# v1_full_project.net
KiCad netlist of a schematic drawn in EasyEDA Pro
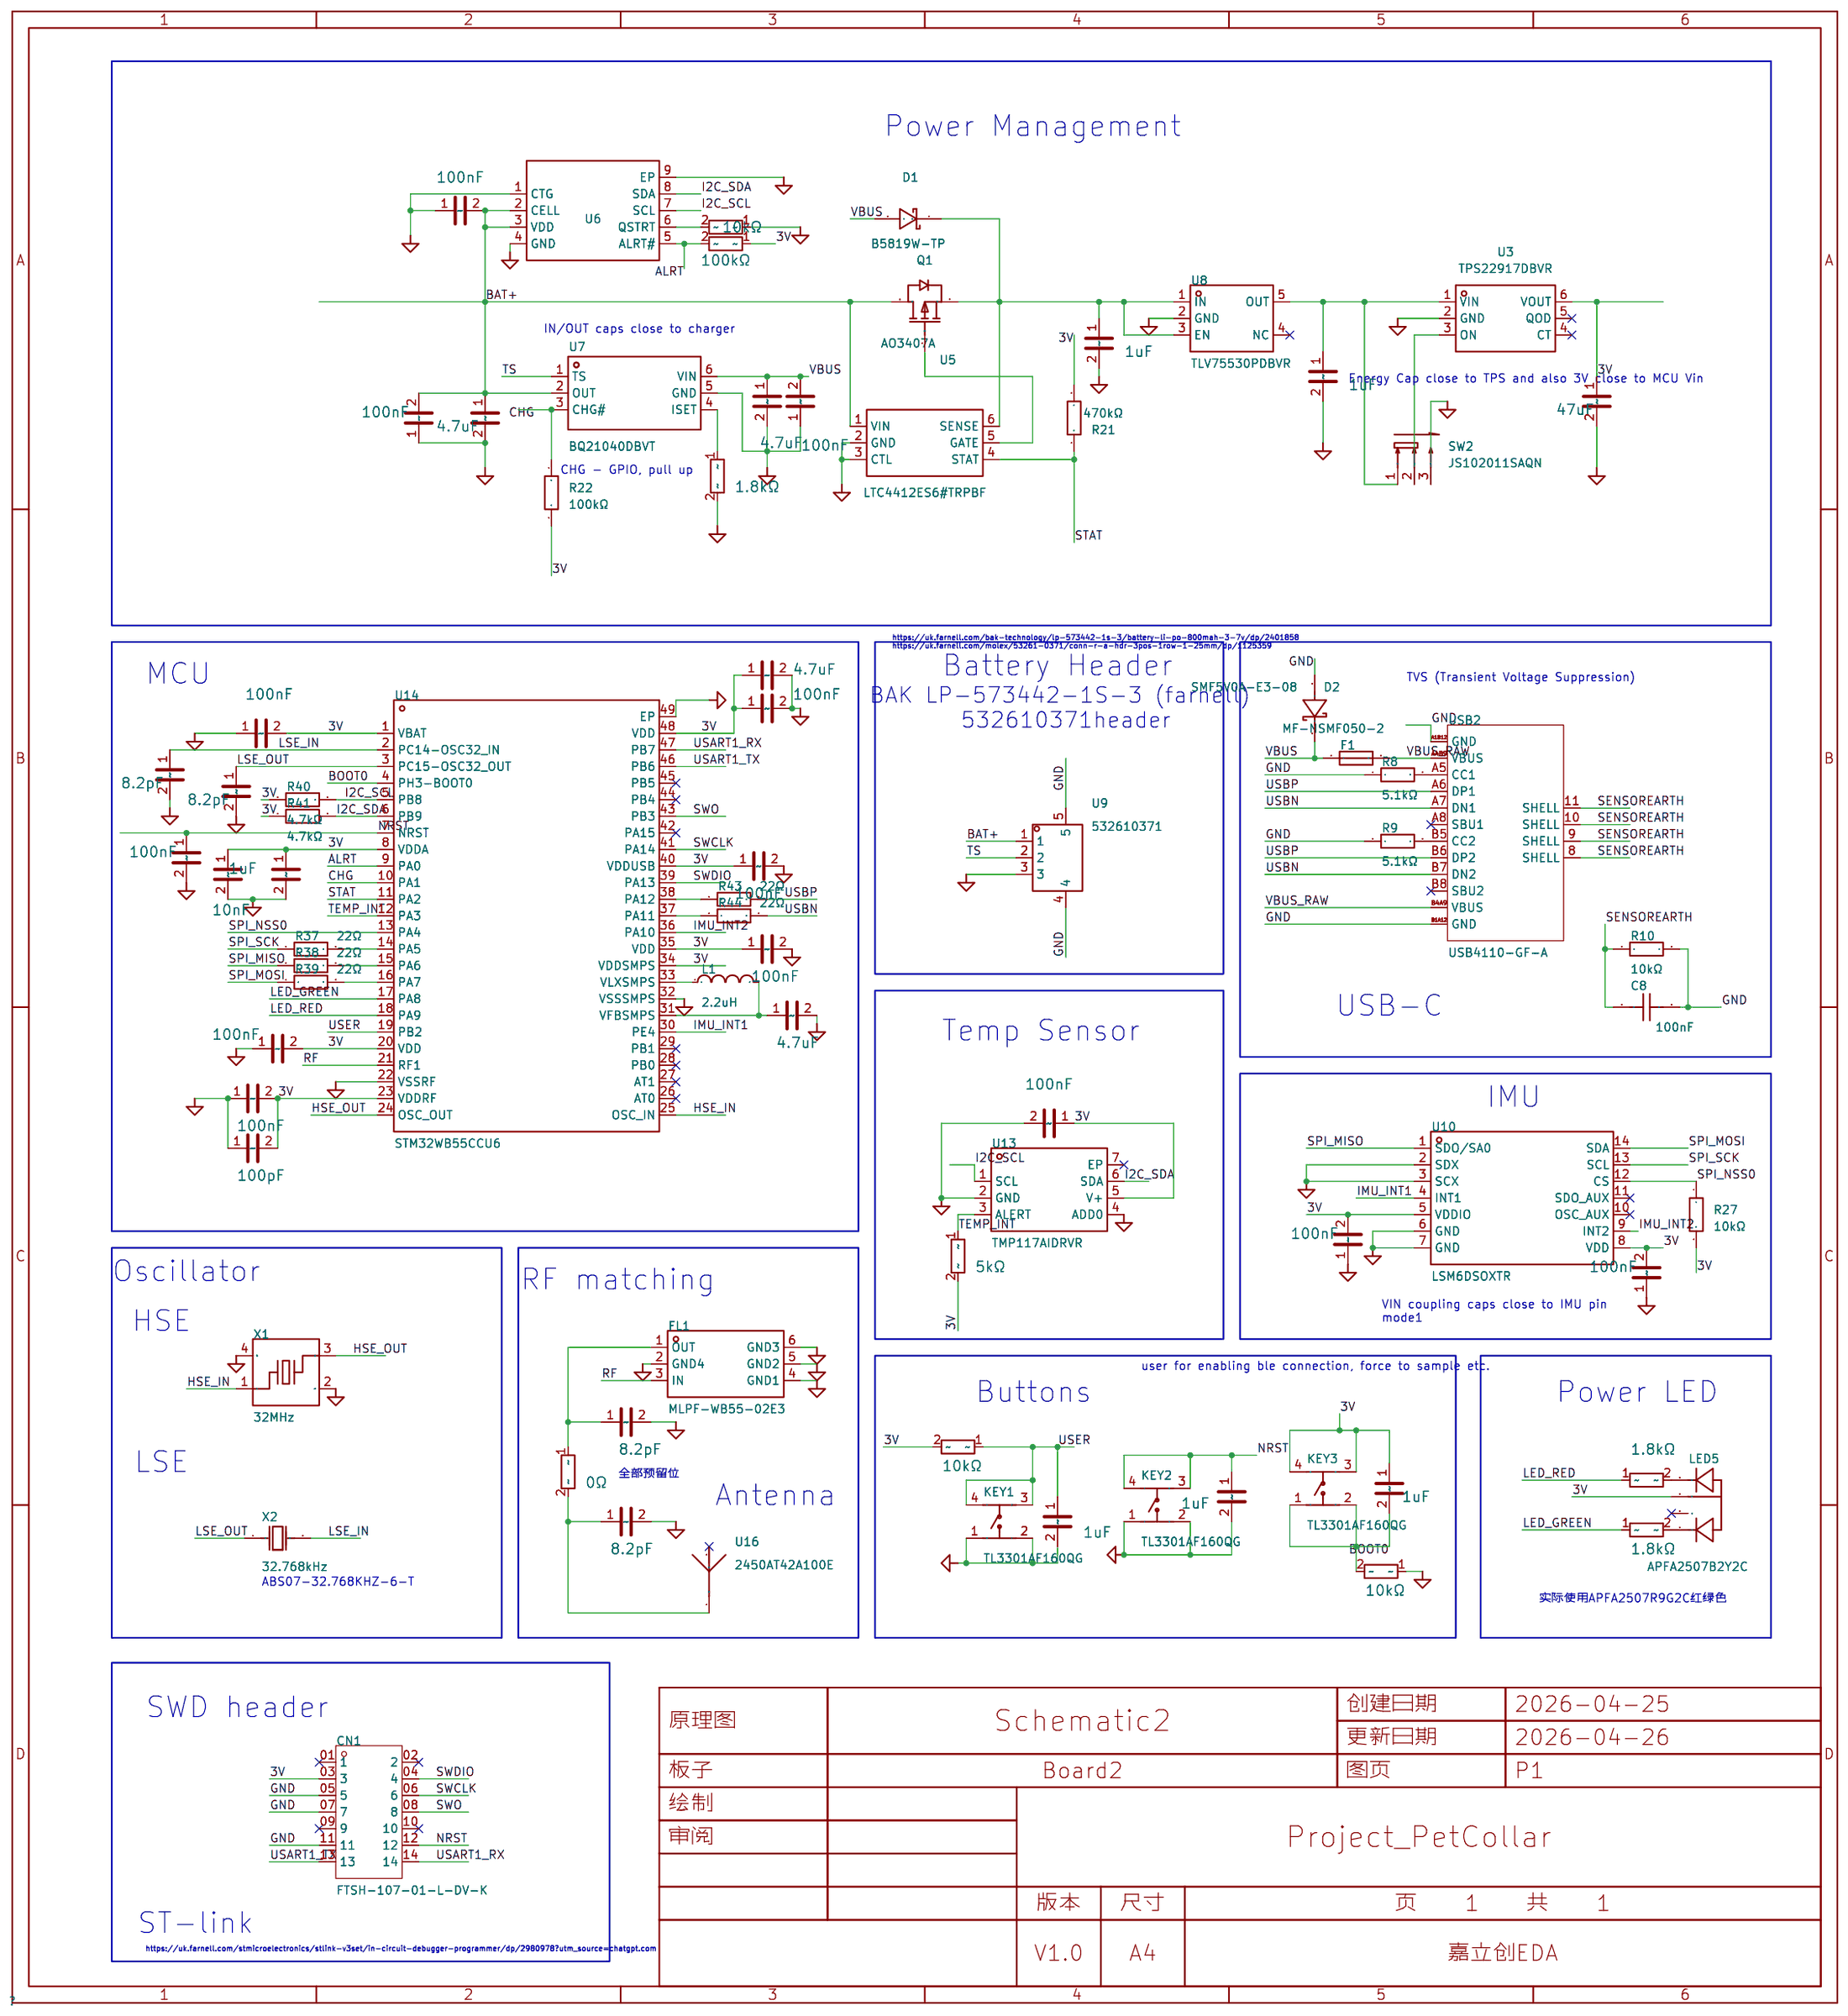
[diagram p0: schematic sheet]

(export (version "E")
  (design (tool "Eeschema 10.0.6"))
  (components
    (comp (ref "C1")
      (value "100nF")
      (description "容值:100nF;精度:±10%;额定电压:50V;温度系数:X7R;")
      (fields
        (field (name "Manufacturer Part") "CL10B104KB8NNNC")
        (field (name "Manufacturer") "SAMSUNG(三星)")
      )
      (libsource (lib "easyedapro") (part "Device_C"))
    )
    (comp (ref "C2")
      (value "1uF")
      (description "容值:1uF;精度:±10%;额定电压:25V;温度系数:X7R;")
      (fields
        (field (name "Manufacturer Part") "CL10B105KA8NNNC")
        (field (name "Manufacturer") "SAMSUNG(三星)")
      )
      (libsource (lib "easyedapro") (part "Device_C"))
    )
    (comp (ref "C3")
      (value "1uF")
      (description "容值:1uF;精度:±10%;额定电压:25V;温度系数:X7R;")
      (fields
        (field (name "Manufacturer Part") "CL10B105KA8NNNC")
        (field (name "Manufacturer") "SAMSUNG(三星)")
      )
      (libsource (lib "easyedapro") (part "Device_C"))
    )
    (comp (ref "C5")
      (value "47uF")
      (description "容值:47uF;精度:±20%;额定电压:6.3V;温度系数:X5R;")
      (fields
        (field (name "Manufacturer Part") "CL21A476MQYNNNE")
        (field (name "Manufacturer") "SAMSUNG(三星)")
      )
      (libsource (lib "easyedapro") (part "Device_C"))
    )
    (comp (ref "C8")
      (value "100nF")
      (fields
        (field (name "Manufacturer Part") "CL10B104KB8NNNC")
        (field (name "Manufacturer") "SAMSUNG(三星)")
      )
      (libsource (lib "easyedapro") (part "Capacitance"))
    )
    (comp (ref "C19")
      (value "1uF")
      (description "容值:1uF;精度:±10%;额定电压:25V;温度系数:X7R;")
      (fields
        (field (name "Manufacturer Part") "CL10B105KA8NNNC")
        (field (name "Manufacturer") "SAMSUNG(三星)")
      )
      (libsource (lib "easyedapro") (part "Device_C"))
    )
    (comp (ref "C23")
      (value "4.7uF")
      (description "容值:4.7uF;精度:±10%;额定电压:16V;温度系数:X5R;")
      (fields
        (field (name "Manufacturer Part") "CL10A475KO8NNNC")
        (field (name "Manufacturer") "SAMSUNG(三星)")
      )
      (libsource (lib "easyedapro") (part "Device_C"))
    )
    (comp (ref "C24")
      (value "4.7uF")
      (description "容值:4.7uF;精度:±10%;额定电压:16V;温度系数:X5R;")
      (fields
        (field (name "Manufacturer Part") "CL10A475KO8NNNC")
        (field (name "Manufacturer") "SAMSUNG(三星)")
      )
      (libsource (lib "easyedapro") (part "Device_C"))
    )
    (comp (ref "C25")
      (value "100nF")
      (description "容值:100nF;精度:±10%;额定电压:50V;温度系数:X7R;")
      (fields
        (field (name "Manufacturer Part") "CL10B104KB8NNNC")
        (field (name "Manufacturer") "SAMSUNG(三星)")
      )
      (libsource (lib "easyedapro") (part "Device_C"))
    )
    (comp (ref "C26")
      (value "100nF")
      (description "容值:100nF;精度:±10%;额定电压:50V;温度系数:X7R;")
      (fields
        (field (name "Manufacturer Part") "CL10B104KB8NNNC")
        (field (name "Manufacturer") "SAMSUNG(三星)")
      )
      (libsource (lib "easyedapro") (part "Device_C"))
    )
    (comp (ref "C27")
      (value "100nF")
      (description "容值:100nF;精度:±10%;额定电压:50V;温度系数:X7R;")
      (fields
        (field (name "Manufacturer Part") "CL10B104KB8NNNC")
        (field (name "Manufacturer") "SAMSUNG(三星)")
      )
      (libsource (lib "easyedapro") (part "Device_C"))
    )
    (comp (ref "C28")
      (value "100nF")
      (description "容值:100nF;精度:±10%;额定电压:50V;温度系数:X7R;")
      (fields
        (field (name "Manufacturer Part") "CL10B104KB8NNNC")
        (field (name "Manufacturer") "SAMSUNG(三星)")
      )
      (libsource (lib "easyedapro") (part "Device_C"))
    )
    (comp (ref "C40")
      (value "1uF")
      (description "容值:1uF;精度:±10%;额定电压:25V;温度系数:X7R;")
      (fields
        (field (name "Manufacturer Part") "CL10B105KA8NNNC")
        (field (name "Manufacturer") "SAMSUNG(三星)")
      )
      (libsource (lib "easyedapro") (part "Device_C"))
    )
    (comp (ref "C41")
      (value "100nF")
      (description "容值:100nF;精度:±10%;额定电压:50V;温度系数:X7R;")
      (fields
        (field (name "Manufacturer Part") "CL10B104KB8NNNC")
        (field (name "Manufacturer") "SAMSUNG(三星)")
      )
      (libsource (lib "easyedapro") (part "Device_C"))
    )
    (comp (ref "C42")
      (value "8.2pF")
      (description "容值:8.2pF;额定电压:50V;材质(温度系数):C0G;")
      (fields
        (field (name "Manufacturer Part") "GJM1555C1H8R2BB01D")
        (field (name "Manufacturer") "muRata(村田)")
      )
      (libsource (lib "easyedapro") (part "Device_C"))
    )
    (comp (ref "C43")
      (value "8.2pF")
      (description "容值:8.2pF;额定电压:50V;材质(温度系数):C0G;")
      (fields
        (field (name "Manufacturer Part") "GJM1555C1H8R2BB01D")
        (field (name "Manufacturer") "muRata(村田)")
      )
      (libsource (lib "easyedapro") (part "Device_C"))
    )
    (comp (ref "C46")
      (value "4.7uF")
      (description "容值:4.7uF;精度:±10%;额定电压:16V;温度系数:X5R;")
      (fields
        (field (name "Manufacturer Part") "CL10A475KO8NNNC")
        (field (name "Manufacturer") "SAMSUNG(三星)")
      )
      (libsource (lib "easyedapro") (part "Device_C"))
    )
    (comp (ref "C49")
      (value "100nF")
      (description "容值:100nF;精度:±10%;额定电压:50V;温度系数:X7R;")
      (fields
        (field (name "Manufacturer Part") "CL10B104KB8NNNC")
        (field (name "Manufacturer") "SAMSUNG(三星)")
      )
      (libsource (lib "easyedapro") (part "Device_C"))
    )
    (comp (ref "C50")
      (value "100nF")
      (description "容值:100nF;精度:±10%;额定电压:50V;温度系数:X7R;")
      (fields
        (field (name "Manufacturer Part") "CL10B104KB8NNNC")
        (field (name "Manufacturer") "SAMSUNG(三星)")
      )
      (libsource (lib "easyedapro") (part "Device_C"))
    )
    (comp (ref "C51")
      (value "100nF")
      (description "容值:100nF;精度:±10%;额定电压:50V;温度系数:X7R;")
      (fields
        (field (name "Manufacturer Part") "CL10B104KB8NNNC")
        (field (name "Manufacturer") "SAMSUNG(三星)")
      )
      (libsource (lib "easyedapro") (part "Device_C"))
    )
    (comp (ref "C52")
      (value "4.7uF")
      (description "容值:4.7uF;精度:±10%;额定电压:16V;温度系数:X5R;")
      (fields
        (field (name "Manufacturer Part") "CL10A475KO8NNNC")
        (field (name "Manufacturer") "SAMSUNG(三星)")
      )
      (libsource (lib "easyedapro") (part "Device_C"))
    )
    (comp (ref "C53")
      (value "10nF")
      (description "容值:10nF;精度:±5%;额定电压:50V;材质(温度系数):C0G;")
      (fields
        (field (name "Manufacturer Part") "GRM1885C1H103JA01D")
        (field (name "Manufacturer") "muRata(村田)")
      )
      (libsource (lib "easyedapro") (part "Device_C"))
    )
    (comp (ref "C54")
      (value "1uF")
      (description "容值:1uF;精度:±10%;额定电压:25V;温度系数:X7R;")
      (fields
        (field (name "Manufacturer Part") "CL10B105KA8NNNC")
        (field (name "Manufacturer") "SAMSUNG(三星)")
      )
      (libsource (lib "easyedapro") (part "Device_C"))
    )
    (comp (ref "C55")
      (value "100nF")
      (description "容值:100nF;精度:±10%;额定电压:50V;温度系数:X7R;")
      (fields
        (field (name "Manufacturer Part") "CL10B104KB8NNNC")
        (field (name "Manufacturer") "SAMSUNG(三星)")
      )
      (libsource (lib "easyedapro") (part "Device_C"))
    )
    (comp (ref "C56")
      (value "100nF")
      (description "容值:100nF;精度:±10%;额定电压:50V;温度系数:X7R;")
      (fields
        (field (name "Manufacturer Part") "CL10B104KB8NNNC")
        (field (name "Manufacturer") "SAMSUNG(三星)")
      )
      (libsource (lib "easyedapro") (part "Device_C"))
    )
    (comp (ref "C57")
      (value "100pF")
      (description "容值:100pF;精度:±5%;额定电压:50V;温度系数:C0G;")
      (fields
        (field (name "Manufacturer Part") "CL10C101JB8NNNC")
        (field (name "Manufacturer") "SAMSUNG(三星)")
      )
      (libsource (lib "easyedapro") (part "Device_C"))
    )
    (comp (ref "C58")
      (value "100nF")
      (description "容值:100nF;精度:±10%;额定电压:50V;温度系数:X7R;")
      (fields
        (field (name "Manufacturer Part") "CL10B104KB8NNNC")
        (field (name "Manufacturer") "SAMSUNG(三星)")
      )
      (libsource (lib "easyedapro") (part "Device_C"))
    )
    (comp (ref "C59")
      (value "100nF")
      (description "容值:100nF;精度:±10%;额定电压:50V;温度系数:X7R;")
      (fields
        (field (name "Manufacturer Part") "CL10B104KB8NNNC")
        (field (name "Manufacturer") "SAMSUNG(三星)")
      )
      (libsource (lib "easyedapro") (part "Device_C"))
    )
    (comp (ref "C60")
      (value "1uF")
      (description "容值:1uF;精度:±10%;额定电压:25V;温度系数:X7R;")
      (fields
        (field (name "Manufacturer Part") "CL10B105KA8NNNC")
        (field (name "Manufacturer") "SAMSUNG(三星)")
      )
      (libsource (lib "easyedapro") (part "Device_C"))
    )
    (comp (ref "C61")
      (value "8.2pF")
      (description "容值:8.2pF;额定电压:50V;材质(温度系数):C0G;")
      (fields
        (field (name "Manufacturer Part") "GJM1555C1H8R2BB01D")
        (field (name "Manufacturer") "muRata(村田)")
      )
      (libsource (lib "easyedapro") (part "Device_C"))
    )
    (comp (ref "C62")
      (value "8.2pF")
      (description "容值:8.2pF;额定电压:50V;材质(温度系数):C0G;")
      (fields
        (field (name "Manufacturer Part") "GJM1555C1H8R2BB01D")
        (field (name "Manufacturer") "muRata(村田)")
      )
      (libsource (lib "easyedapro") (part "Device_C"))
    )
    (comp (ref "CN1")
      (value "FTSH-107-01-L-DV-K")
      (footprint "easyedapro:HDR-SMD_14P-P1.27_FTSH-107-01-L-DV-K")
      (fields (field (name "Manufacturer") "SAMTEC"))
      (libsource (lib "easyedapro") (part "FTSH-107-01-L-DV-K"))
    )
    (comp (ref "D1")
      (value "B5819W-TP")
      (footprint "easyedapro:SOD-123_L2.8-W1.8-LS3.7-RD")
      (description "二极管配置:-;正向压降(Vf):600mV@1A;直流反向耐压(Vr):40V;整流电流:1A;")
      (fields (field (name "Manufacturer") "MCC(美微科)"))
      (libsource (lib "easyedapro") (part "B5819W-TP"))
    )
    (comp (ref "D2")
      (value "SMF5V0A-E3-08")
      (footprint "easyedapro:SMF_L2.8-W1.8-LS3.7-RD")
      (fields (field (name "Manufacturer") "VISHAY(威世)"))
      (libsource (lib "easyedapro") (part "SMF5V0A-E3-08"))
    )
    (comp (ref "F1")
      (value "MF-NSMF050-2")
      (footprint "easyedapro:F1206")
      (fields (field (name "Manufacturer") "BOURNS"))
      (libsource (lib "easyedapro") (part "MF-NSMF050-2"))
    )
    (comp (ref "FL1")
      (value "MLPF-WB55-02E3")
      (footprint "easyedapro:FILTER-SMD_6P-L1.6-W1.0-P0.50-BL")
      (fields (field (name "Manufacturer") "ST(意法半导体)"))
      (libsource (lib "easyedapro") (part "MLPF-WB55-02E3"))
    )
    (comp (ref "KEY1")
      (value "TL3301AF160QG")
      (footprint "easyedapro:KEY-SMD_4P-L6.0-W6.0-P4.50-LS10.0")
      (fields (field (name "Manufacturer") "E-Switch"))
      (libsource (lib "easyedapro") (part "TL3301AF160QG"))
    )
    (comp (ref "KEY2")
      (value "TL3301AF160QG")
      (footprint "easyedapro:KEY-SMD_4P-L6.0-W6.0-P4.50-LS10.0")
      (fields (field (name "Manufacturer") "E-Switch"))
      (libsource (lib "easyedapro") (part "TL3301AF160QG"))
    )
    (comp (ref "KEY3")
      (value "TL3301AF160QG")
      (footprint "easyedapro:KEY-SMD_4P-L6.0-W6.0-P4.50-LS10.0")
      (fields (field (name "Manufacturer") "E-Switch"))
      (libsource (lib "easyedapro") (part "TL3301AF160QG"))
    )
    (comp (ref "L1")
      (value "2.2uH")
      (footprint "easyedapro:L1008")
      (fields
        (field (name "Manufacturer Part") "1239AS-H-2R2M=P2")
        (field (name "Manufacturer") "muRata(村田)")
      )
      (libsource (lib "easyedapro") (part "1239AS-H-2R2M=P2"))
    )
    (comp (ref "LED5")
      (value "APFA2507B2Y2C")
      (footprint "easyedapro:LED-SMD_4P-L2.5-W1.0_APFA2507LQBDSEEZGKC")
      (fields (field (name "Manufacturer") "Kingbright"))
      (libsource (lib "easyedapro") (part "APFA2507B2Y2C"))
    )
    (comp (ref "Q1")
      (value "AO3407A")
      (footprint "easyedapro:SOT-23-3_L2.9-W1.6-P1.90-LS2.8-BR")
      (fields (field (name "Manufacturer") "AOS"))
      (libsource (lib "easyedapro") (part "AO3407A"))
    )
    (comp (ref "R1")
      (value "10kΩ")
      (description "电阻类型:厚膜电阻;阻值:10kΩ;精度:±1%;功率:100mW;最大工作电压:75V;温度系数:±100ppm/℃;")
      (fields (field (name "Manufacturer Part") "RC0603FR-0710KL") (field (name "Manufacturer") "YAGEO(国巨)"))
      (libsource (lib "easyedapro") (part "Device_R"))
    )
    (comp (ref "R2")
      (value "100kΩ")
      (description "电阻类型:厚膜电阻;阻值:100kΩ;精度:±1%;功率:100mW;最大工作电压:75V;温度系数:±100ppm/℃;")
      (fields (field (name "Manufacturer Part") "RC0603FR-07100KL") (field (name "Manufacturer") "YAGEO(国巨)"))
      (libsource (lib "easyedapro") (part "Device_R"))
    )
    (comp (ref "R8")
      (value "5.1kΩ")
      (fields (field (name "Manufacturer Part") "FRC0603F5102TS") (field (name "Manufacturer") "FOJAN(富捷)"))
      (libsource (lib "easyedapro") (part "电阻"))
    )
    (comp (ref "R9")
      (value "5.1kΩ")
      (fields (field (name "Manufacturer Part") "FRC0603F5102TS") (field (name "Manufacturer") "FOJAN(富捷)"))
      (libsource (lib "easyedapro") (part "电阻"))
    )
    (comp (ref "R10")
      (value "10kΩ")
      (fields (field (name "Manufacturer Part") "RC0603FR-0710KL") (field (name "Manufacturer") "YAGEO(国巨)"))
      (libsource (lib "easyedapro") (part "电阻"))
    )
    (comp (ref "R20")
      (value "1.8kΩ")
      (description "电阻类型:厚膜电阻;阻值:1.8kΩ;精度:±1%;功率:100mW;工作电压:75V;温度系数:±100ppm/℃;")
      (fields
        (field (name "Manufacturer Part") "0603WAF1801T5E")
        (field (name "Manufacturer") "UNI-ROYAL(厚声)")
      )
      (libsource (lib "easyedapro") (part "Device_R"))
    )
    (comp (ref "R21")
      (value "470kΩ")
      (fields (field (name "Manufacturer Part") "FRC0603F4703TS") (field (name "Manufacturer") "FOJAN(富捷)"))
      (libsource (lib "easyedapro") (part "电阻"))
    )
    (comp (ref "R22")
      (value "100kΩ")
      (fields (field (name "Manufacturer Part") "RC0603FR-07100KL") (field (name "Manufacturer") "YAGEO(国巨)"))
      (libsource (lib "easyedapro") (part "电阻"))
    )
    (comp (ref "R27")
      (value "10kΩ")
      (fields (field (name "Manufacturer Part") "RC0603FR-0710KL") (field (name "Manufacturer") "YAGEO(国巨)"))
      (libsource (lib "easyedapro") (part "电阻"))
    )
    (comp (ref "R33")
      (value "10kΩ")
      (description "电阻类型:厚膜电阻;阻值:10kΩ;精度:±1%;功率:100mW;最大工作电压:75V;温度系数:±100ppm/℃;")
      (fields (field (name "Manufacturer Part") "RC0603FR-0710KL") (field (name "Manufacturer") "YAGEO(国巨)"))
      (libsource (lib "easyedapro") (part "Device_R"))
    )
    (comp (ref "R35")
      (value "5kΩ")
      (description "电阻类型:薄膜电阻;阻值:5kΩ;精度:±0.1%;功率:100mW;温度系数:±50ppm/℃;")
      (fields (field (name "Manufacturer Part") "RT0603BRE075KL") (field (name "Manufacturer") "YAGEO(国巨)"))
      (libsource (lib "easyedapro") (part "Device_R"))
    )
    (comp (ref "R36")
      (value "0Ω")
      (description "电阻类型:厚膜电阻;阻值:0Ω;精度:±1%;功率:62.5mW;工作电压:50V;温度系数:-;")
      (fields (field (name "Manufacturer Part") "RC0402FR-070RL") (field (name "Manufacturer") "YAGEO(国巨)"))
      (libsource (lib "easyedapro") (part "Device_R"))
    )
    (comp (ref "R37")
      (value "22Ω")
      (fields (field (name "Manufacturer Part") "FRC0603J220 TS") (field (name "Manufacturer") "FOJAN(富捷)"))
      (libsource (lib "easyedapro") (part "电阻"))
    )
    (comp (ref "R38")
      (value "22Ω")
      (fields (field (name "Manufacturer Part") "FRC0603J220 TS") (field (name "Manufacturer") "FOJAN(富捷)"))
      (libsource (lib "easyedapro") (part "电阻"))
    )
    (comp (ref "R39")
      (value "22Ω")
      (fields (field (name "Manufacturer Part") "FRC0603J220 TS") (field (name "Manufacturer") "FOJAN(富捷)"))
      (libsource (lib "easyedapro") (part "电阻"))
    )
    (comp (ref "R40")
      (value "4.7kΩ")
      (fields (field (name "Manufacturer Part") "RC0603FR-074K7L") (field (name "Manufacturer") "YAGEO(国巨)"))
      (libsource (lib "easyedapro") (part "电阻"))
    )
    (comp (ref "R41")
      (value "4.7kΩ")
      (fields (field (name "Manufacturer Part") "RC0603FR-074K7L") (field (name "Manufacturer") "YAGEO(国巨)"))
      (libsource (lib "easyedapro") (part "电阻"))
    )
    (comp (ref "R42")
      (value "10kΩ")
      (description "电阻类型:厚膜电阻;阻值:10kΩ;精度:±1%;功率:100mW;最大工作电压:75V;温度系数:±100ppm/℃;")
      (fields (field (name "Manufacturer Part") "RC0603FR-0710KL") (field (name "Manufacturer") "YAGEO(国巨)"))
      (libsource (lib "easyedapro") (part "Device_R"))
    )
    (comp (ref "R43")
      (value "22Ω")
      (fields (field (name "Manufacturer Part") "FRC0603J220 TS") (field (name "Manufacturer") "FOJAN(富捷)"))
      (libsource (lib "easyedapro") (part "电阻"))
    )
    (comp (ref "R44")
      (value "22Ω")
      (fields (field (name "Manufacturer Part") "FRC0603J220 TS") (field (name "Manufacturer") "FOJAN(富捷)"))
      (libsource (lib "easyedapro") (part "电阻"))
    )
    (comp (ref "R45")
      (value "1.8kΩ")
      (description "电阻类型:厚膜电阻;阻值:1.8kΩ;精度:±1%;功率:100mW;工作电压:75V;温度系数:±100ppm/℃;")
      (fields
        (field (name "Manufacturer Part") "0603WAF1801T5E")
        (field (name "Manufacturer") "UNI-ROYAL(厚声)")
      )
      (libsource (lib "easyedapro") (part "Device_R"))
    )
    (comp (ref "R46")
      (value "1.8kΩ")
      (description "电阻类型:厚膜电阻;阻值:1.8kΩ;精度:±1%;功率:100mW;工作电压:75V;温度系数:±100ppm/℃;")
      (fields
        (field (name "Manufacturer Part") "0603WAF1801T5E")
        (field (name "Manufacturer") "UNI-ROYAL(厚声)")
      )
      (libsource (lib "easyedapro") (part "Device_R"))
    )
    (comp (ref "SW2")
      (value "JS102011SAQN")
      (footprint "easyedapro:SW-SMD_JS102011SAQN")
      (fields (field (name "Manufacturer") "C&K"))
      (libsource (lib "easyedapro") (part "JS102011SAQN"))
    )
    (comp (ref "U3")
      (value "TPS22917DBVR")
      (footprint "easyedapro:SOT-23-6_L2.9-W1.6-P0.95-LS2.8-BR")
      (description "类型:负载开关;通道数:1;输入控制逻辑:高电平有效;最大连续电流:2A;工作电压:0V~5.5V;导通电阻:80mΩ;")
      (fields (field (name "Manufacturer") "TI(德州仪器)"))
      (libsource (lib "easyedapro") (part "TPS22917DBVR"))
    )
    (comp (ref "U5")
      (value "LTC4412ES6#TRPBF")
      (footprint "easyedapro:TSOT-23-6_L2.9-W1.6-P0.95-LS2.8-BR")
      (description "负载类型:MOSFET;工作电压:2.5V~28V;")
      (fields (field (name "Manufacturer") "ADI(亚德诺)"))
      (libsource (lib "easyedapro") (part "LTC4412ES6#TRPBF"))
    )
    (comp (ref "U6")
      (value "MAX17048G+T10")
      (footprint "easyedapro:TDFN-8_L2.0-W2.0-P0.50-BL-EP1.2")
      (description "工作电压:2.5V~4.5V;电池类型:锂离子/聚合物;电池节数:1;")
      (fields (field (name "Manufacturer") "ADI(亚德诺)/MAXIM(美信)"))
      (libsource (lib "easyedapro") (part "MAX17048G+T10"))
    )
    (comp (ref "U7")
      (value "BQ21040DBVT")
      (footprint "easyedapro:SOT-23-6_L2.9-W1.6-P0.95-LS2.8-BR")
      (fields (field (name "Manufacturer") "TI(德州仪器)"))
      (libsource (lib "easyedapro") (part "BQ21040DBVT"))
    )
    (comp (ref "U8")
      (value "TLV75530PDBVR")
      (footprint "easyedapro:SOT-23-5_L3.0-W1.7-P0.95-LS2.8-BR")
      (fields (field (name "Manufacturer") "TI(德州仪器)"))
      (libsource (lib "easyedapro") (part "TLV75530PDBVR"))
    )
    (comp (ref "U9")
      (value "532610371")
      (footprint "easyedapro:CONN-TH_532610371")
      (fields (field (name "Manufacturer") "MOLEX"))
      (libsource (lib "easyedapro") (part "532610371"))
    )
    (comp (ref "U10")
      (value "LSM6DSOXTR")
      (footprint "easyedapro:LGA-14L_L3.0-W2.5-P0.50-TL")
      (fields (field (name "Manufacturer") "ST(意法半导体)"))
      (libsource (lib "easyedapro") (part "LSM6DSOXTR"))
    )
    (comp (ref "U13")
      (value "TMP117AIDRVR")
      (footprint "easyedapro:WSON-6_L2.0-W2.0-P0.65-TL-EP")
      (fields (field (name "Manufacturer") "TI(德州仪器)"))
      (libsource (lib "easyedapro") (part "TMP117AIDRVR"))
    )
    (comp (ref "U14")
      (value "STM32WB55CCU6")
      (footprint "easyedapro:VQFN-48_L7.0-W7.0-P0.50-BL-EP5.5")
      (fields (field (name "Manufacturer") "ST(意法半导体)"))
      (libsource (lib "easyedapro") (part "STM32WB55CCU6"))
    )
    (comp (ref "U16")
      (value "2450AT42A100E")
      (footprint "easyedapro:ANT-SMD_L5.0-W2.0")
      (fields (field (name "Manufacturer") "JOHANSON(约翰逊)"))
      (libsource (lib "easyedapro") (part "2450AT42A100E"))
    )
    (comp (ref "USB2")
      (value "USB4110-GF-A")
      (footprint "easyedapro:USB-C-SMD_TYPE-C-16P-USB4110-GF-A")
      (description "连接器类型:Type-C;协议标准:USB 2.0;公母:母;安装方式:卧贴;端口数量:1;额定电流 - 电源:5A;工作温度:-40°C~+85°C;")
      (fields (field (name "Manufacturer") "GCT"))
      (libsource (lib "easyedapro") (part "USB4110-GF-A"))
    )
    (comp (ref "X1")
      (value "32MHz")
      (footprint "easyedapro:CRYSTAL-SMD_4P-L2.0-W1.6-BL")
      (fields
        (field (name "Manufacturer Part") "NX2016SA-32MHZ-EXS00A-CS06654")
        (field (name "Manufacturer") "NDK")
      )
      (libsource (lib "easyedapro") (part "NX2016SA-32MHZ-EXS00A-CS06654"))
    )
    (comp (ref "X2")
      (value "32.768kHz")
      (footprint "easyedapro:CRYSTAL-SMD_L3.2-W1.5-2")
      (fields
        (field (name "Manufacturer Part") "ABS07-32.768KHZ-6-T")
        (field (name "Manufacturer") "ABRACON")
      )
      (libsource (lib "easyedapro") (part "ABS07-32.768KHZ-6-T"))
    )
  )
  (nets
    (net (code "1") (name "/3V") (class "Default")
      (node (ref "C27") (pin "2") (pinfunction "~_2") (pintype "unspecified"))
      (node (ref "C28") (pin "2") (pinfunction "~_2") (pintype "unspecified"))
      (node (ref "C41") (pin "1") (pinfunction "~_1") (pintype "unspecified"))
      (node (ref "C49") (pin "2") (pinfunction "~_2") (pintype "unspecified"))
      (node (ref "C5") (pin "1") (pinfunction "~_1") (pintype "unspecified"))
      (node (ref "C50") (pin "1") (pinfunction "~_1") (pintype "unspecified"))
      (node (ref "C51") (pin "1") (pinfunction "~_1") (pintype "unspecified"))
      (node (ref "C52") (pin "1") (pinfunction "~_1") (pintype "unspecified"))
      (node (ref "C53") (pin "1") (pinfunction "~_1") (pintype "unspecified"))
      (node (ref "C54") (pin "1") (pinfunction "~_1") (pintype "unspecified"))
      (node (ref "C55") (pin "1") (pinfunction "~_1") (pintype "unspecified"))
      (node (ref "C56") (pin "2") (pinfunction "~_2") (pintype "unspecified"))
      (node (ref "C57") (pin "2") (pinfunction "~_2") (pintype "unspecified"))
      (node (ref "C58") (pin "2") (pinfunction "~_2") (pintype "unspecified"))
      (node (ref "C60") (pin "1") (pinfunction "~_1") (pintype "unspecified"))
      (node (ref "CN1") (pin "03") (pinfunction "3_03") (pintype "unspecified"))
      (node (ref "KEY3") (pin "3") (pinfunction "3_3") (pintype "unspecified"))
      (node (ref "KEY3") (pin "4") (pinfunction "4_4") (pintype "unspecified"))
      (node (ref "LED5") (pin "2") (pinfunction "2_2") (pintype "unspecified"))
      (node (ref "R2") (pin "1") (pinfunction "~_1") (pintype "unspecified"))
      (node (ref "R21") (pin "2") (pinfunction "2_2") (pintype "input"))
      (node (ref "R22") (pin "2") (pinfunction "2_2") (pintype "input"))
      (node (ref "R27") (pin "2") (pinfunction "2_2") (pintype "input"))
      (node (ref "R33") (pin "2") (pinfunction "~_2") (pintype "unspecified"))
      (node (ref "R35") (pin "2") (pinfunction "~_2") (pintype "unspecified"))
      (node (ref "R40") (pin "1") (pinfunction "1_1") (pintype "input"))
      (node (ref "R41") (pin "1") (pinfunction "1_1") (pintype "input"))
      (node (ref "U10") (pin "5") (pinfunction "VDDIO_5") (pintype "unspecified"))
      (node (ref "U10") (pin "8") (pinfunction "VDD_8") (pintype "unspecified"))
      (node (ref "U13") (pin "5") (pinfunction "V+_5") (pintype "unspecified"))
      (node (ref "U14") (pin "1") (pinfunction "VBAT_1") (pintype "unspecified"))
      (node (ref "U14") (pin "20") (pinfunction "VDD_20") (pintype "unspecified"))
      (node (ref "U14") (pin "23") (pinfunction "VDDRF_23") (pintype "unspecified"))
      (node (ref "U14") (pin "34") (pinfunction "VDDSMPS_34") (pintype "unspecified"))
      (node (ref "U14") (pin "35") (pinfunction "VDD_35") (pintype "unspecified"))
      (node (ref "U14") (pin "40") (pinfunction "VDDUSB_40") (pintype "unspecified"))
      (node (ref "U14") (pin "48") (pinfunction "VDD_48") (pintype "unspecified"))
      (node (ref "U14") (pin "8") (pinfunction "VDDA_8") (pintype "unspecified"))
      (node (ref "U3") (pin "6") (pinfunction "VOUT_6") (pintype "unspecified"))
    )
    (net (code "2") (name "/ALRT") (class "Default")
      (node (ref "R2") (pin "2") (pinfunction "~_2") (pintype "unspecified"))
      (node (ref "U14") (pin "9") (pinfunction "PA0_9") (pintype "unspecified"))
      (node (ref "U6") (pin "5") (pinfunction "ALRT#_5") (pintype "unspecified"))
    )
    (net (code "3") (name "/BAT+") (class "Default")
      (node (ref "C1") (pin "2") (pinfunction "~_2") (pintype "unspecified"))
      (node (ref "C24") (pin "1") (pinfunction "~_1") (pintype "unspecified"))
      (node (ref "C25") (pin "2") (pinfunction "~_2") (pintype "unspecified"))
      (node (ref "Q1") (pin "3") (pinfunction "D_3") (pintype "unspecified"))
      (node (ref "U5") (pin "1") (pinfunction "VIN_1") (pintype "unspecified"))
      (node (ref "U6") (pin "2") (pinfunction "CELL_2") (pintype "unspecified"))
      (node (ref "U6") (pin "3") (pinfunction "VDD_3") (pintype "unspecified"))
      (node (ref "U7") (pin "2") (pinfunction "OUT_2") (pintype "unspecified"))
      (node (ref "U9") (pin "1") (pinfunction "1_1") (pintype "unspecified"))
    )
    (net (code "4") (name "/BOOT0") (class "Default")
      (node (ref "C60") (pin "2") (pinfunction "~_2") (pintype "unspecified"))
      (node (ref "KEY3") (pin "1") (pinfunction "1_1") (pintype "unspecified"))
      (node (ref "KEY3") (pin "2") (pinfunction "2_2") (pintype "unspecified"))
      (node (ref "R42") (pin "2") (pinfunction "~_2") (pintype "unspecified"))
      (node (ref "U14") (pin "4") (pinfunction "PH3-BOOT0_4") (pintype "unspecified"))
    )
    (net (code "5") (name "/CHG") (class "Default")
      (node (ref "R22") (pin "1") (pinfunction "1_1") (pintype "input"))
      (node (ref "U14") (pin "10") (pinfunction "PA1_10") (pintype "unspecified"))
      (node (ref "U7") (pin "3") (pinfunction "CHG#_3") (pintype "unspecified"))
    )
    (net (code "6") (name "/HSE_IN") (class "Default")
      (node (ref "U14") (pin "25") (pinfunction "OSC_IN_25") (pintype "unspecified"))
      (node (ref "X1") (pin "1") (pinfunction "1_1") (pintype "input"))
    )
    (net (code "7") (name "/HSE_OUT") (class "Default")
      (node (ref "U14") (pin "24") (pinfunction "OSC_OUT_24") (pintype "unspecified"))
      (node (ref "X1") (pin "3") (pinfunction "3_3") (pintype "input"))
    )
    (net (code "8") (name "/I2C_SCL") (class "Default")
      (node (ref "R40") (pin "2") (pinfunction "2_2") (pintype "input"))
      (node (ref "U13") (pin "1") (pinfunction "SCL_1") (pintype "unspecified"))
      (node (ref "U14") (pin "5") (pinfunction "PB8_5") (pintype "unspecified"))
      (node (ref "U6") (pin "7") (pinfunction "SCL_7") (pintype "unspecified"))
    )
    (net (code "9") (name "/I2C_SDA") (class "Default")
      (node (ref "R41") (pin "2") (pinfunction "2_2") (pintype "input"))
      (node (ref "U13") (pin "6") (pinfunction "SDA_6") (pintype "unspecified"))
      (node (ref "U14") (pin "6") (pinfunction "PB9_6") (pintype "unspecified"))
      (node (ref "U6") (pin "8") (pinfunction "SDA_8") (pintype "unspecified"))
    )
    (net (code "10") (name "/IMU_INT1") (class "Default")
      (node (ref "U10") (pin "4") (pinfunction "INT1_4") (pintype "unspecified"))
      (node (ref "U14") (pin "30") (pinfunction "PE4_30") (pintype "unspecified"))
    )
    (net (code "11") (name "/IMU_INT2") (class "Default")
      (node (ref "U10") (pin "9") (pinfunction "INT2_9") (pintype "unspecified"))
      (node (ref "U14") (pin "36") (pinfunction "PA10_36") (pintype "unspecified"))
    )
    (net (code "12") (name "/LED_GREEN") (class "Default")
      (node (ref "R46") (pin "1") (pinfunction "~_1") (pintype "unspecified"))
      (node (ref "U14") (pin "17") (pinfunction "PA8_17") (pintype "unspecified"))
    )
    (net (code "13") (name "/LED_RED") (class "Default")
      (node (ref "R45") (pin "1") (pinfunction "~_1") (pintype "unspecified"))
      (node (ref "U14") (pin "18") (pinfunction "PA9_18") (pintype "unspecified"))
    )
    (net (code "14") (name "/LSE_IN") (class "Default")
      (node (ref "C42") (pin "1") (pinfunction "~_1") (pintype "unspecified"))
      (node (ref "U14") (pin "2") (pinfunction "PC14-OSC32_IN_2") (pintype "unspecified"))
      (node (ref "X2") (pin "2") (pinfunction "OSC2_2") (pintype "input"))
    )
    (net (code "15") (name "/LSE_OUT") (class "Default")
      (node (ref "C43") (pin "1") (pinfunction "~_1") (pintype "unspecified"))
      (node (ref "U14") (pin "3") (pinfunction "PC15-OSC32_OUT_3") (pintype "unspecified"))
      (node (ref "X2") (pin "1") (pinfunction "OSC1_1") (pintype "input"))
    )
    (net (code "16") (name "/NRST") (class "Default")
      (node (ref "C19") (pin "1") (pinfunction "~_1") (pintype "unspecified"))
      (node (ref "C59") (pin "1") (pinfunction "~_1") (pintype "unspecified"))
      (node (ref "CN1") (pin "12") (pinfunction "12_12") (pintype "unspecified"))
      (node (ref "KEY2") (pin "3") (pinfunction "3_3") (pintype "unspecified"))
      (node (ref "KEY2") (pin "4") (pinfunction "4_4") (pintype "unspecified"))
      (node (ref "U14") (pin "7") (pinfunction "NRST_7") (pintype "unspecified"))
    )
    (net (code "17") (name "/RF") (class "Default")
      (node (ref "FL1") (pin "3") (pinfunction "IN_3") (pintype "unspecified"))
      (node (ref "U14") (pin "21") (pinfunction "RF1_21") (pintype "unspecified"))
    )
    (net (code "18") (name "/SENSOREARTH") (class "Default")
      (node (ref "C8") (pin "1") (pinfunction "1_1") (pintype "input"))
      (node (ref "R10") (pin "1") (pinfunction "1_1") (pintype "input"))
      (node (ref "USB2") (pin "10") (pinfunction "SHELL_10") (pintype "unspecified"))
      (node (ref "USB2") (pin "11") (pinfunction "SHELL_11") (pintype "unspecified"))
      (node (ref "USB2") (pin "8") (pinfunction "SHELL_8") (pintype "unspecified"))
      (node (ref "USB2") (pin "9") (pinfunction "SHELL_9") (pintype "unspecified"))
    )
    (net (code "19") (name "/SPI_MISO") (class "Default")
      (node (ref "R38") (pin "1") (pinfunction "1_1") (pintype "input"))
      (node (ref "U10") (pin "1") (pinfunction "SDO/SA0_1") (pintype "unspecified"))
    )
    (net (code "20") (name "/SPI_MOSI") (class "Default")
      (node (ref "R39") (pin "1") (pinfunction "1_1") (pintype "input"))
      (node (ref "U10") (pin "14") (pinfunction "SDA_14") (pintype "unspecified"))
    )
    (net (code "21") (name "/SPI_NSS0") (class "Default")
      (node (ref "R27") (pin "1") (pinfunction "1_1") (pintype "input"))
      (node (ref "U10") (pin "12") (pinfunction "CS_12") (pintype "unspecified"))
      (node (ref "U14") (pin "13") (pinfunction "PA4_13") (pintype "unspecified"))
    )
    (net (code "22") (name "/SPI_SCK") (class "Default")
      (node (ref "R37") (pin "1") (pinfunction "1_1") (pintype "input"))
      (node (ref "U10") (pin "13") (pinfunction "SCL_13") (pintype "unspecified"))
    )
    (net (code "23") (name "/STAT") (class "Default")
      (node (ref "R21") (pin "1") (pinfunction "1_1") (pintype "input"))
      (node (ref "U14") (pin "11") (pinfunction "PA2_11") (pintype "unspecified"))
      (node (ref "U5") (pin "4") (pinfunction "STAT_4") (pintype "unspecified"))
    )
    (net (code "24") (name "/SWCLK") (class "Default")
      (node (ref "CN1") (pin "06") (pinfunction "6_06") (pintype "unspecified"))
      (node (ref "U14") (pin "41") (pinfunction "PA14_41") (pintype "unspecified"))
    )
    (net (code "25") (name "/SWDIO") (class "Default")
      (node (ref "CN1") (pin "04") (pinfunction "4_04") (pintype "unspecified"))
      (node (ref "U14") (pin "39") (pinfunction "PA13_39") (pintype "unspecified"))
    )
    (net (code "26") (name "/SWO") (class "Default")
      (node (ref "CN1") (pin "08") (pinfunction "8_08") (pintype "unspecified"))
      (node (ref "U14") (pin "43") (pinfunction "PB3_43") (pintype "unspecified"))
    )
    (net (code "27") (name "/TEMP_INT") (class "Default")
      (node (ref "R35") (pin "1") (pinfunction "~_1") (pintype "unspecified"))
      (node (ref "U13") (pin "3") (pinfunction "ALERT_3") (pintype "unspecified"))
      (node (ref "U14") (pin "12") (pinfunction "PA3_12") (pintype "unspecified"))
    )
    (net (code "28") (name "/TS") (class "Default")
      (node (ref "U7") (pin "1") (pinfunction "TS_1") (pintype "unspecified"))
      (node (ref "U9") (pin "2") (pinfunction "2_2") (pintype "unspecified"))
    )
    (net (code "29") (name "/USART1_RX") (class "Default")
      (node (ref "CN1") (pin "14") (pinfunction "14_14") (pintype "unspecified"))
      (node (ref "U14") (pin "47") (pinfunction "PB7_47") (pintype "unspecified"))
    )
    (net (code "30") (name "/USART1_TX") (class "Default")
      (node (ref "CN1") (pin "13") (pinfunction "13_13") (pintype "unspecified"))
      (node (ref "U14") (pin "46") (pinfunction "PB6_46") (pintype "unspecified"))
    )
    (net (code "31") (name "/USBN") (class "Default")
      (node (ref "R44") (pin "2") (pinfunction "2_2") (pintype "input"))
      (node (ref "USB2") (pin "A7") (pinfunction "DN1_A7") (pintype "unspecified"))
      (node (ref "USB2") (pin "B7") (pinfunction "DN2_B7") (pintype "unspecified"))
    )
    (net (code "32") (name "/USBP") (class "Default")
      (node (ref "R43") (pin "2") (pinfunction "2_2") (pintype "input"))
      (node (ref "USB2") (pin "A6") (pinfunction "DP1_A6") (pintype "unspecified"))
      (node (ref "USB2") (pin "B6") (pinfunction "DP2_B6") (pintype "unspecified"))
    )
    (net (code "33") (name "/USER") (class "Default")
      (node (ref "C40") (pin "1") (pinfunction "~_1") (pintype "unspecified"))
      (node (ref "KEY1") (pin "3") (pinfunction "3_3") (pintype "unspecified"))
      (node (ref "KEY1") (pin "4") (pinfunction "4_4") (pintype "unspecified"))
      (node (ref "R33") (pin "1") (pinfunction "~_1") (pintype "unspecified"))
      (node (ref "U14") (pin "19") (pinfunction "PB2_19") (pintype "unspecified"))
    )
    (net (code "34") (name "/VBUS") (class "Default")
      (node (ref "C23") (pin "1") (pinfunction "~_1") (pintype "unspecified"))
      (node (ref "C26") (pin "2") (pinfunction "~_2") (pintype "unspecified"))
      (node (ref "D1") (pin "2") (pinfunction "A_2") (pintype "unspecified"))
      (node (ref "D2") (pin "1") (pinfunction "K_1") (pintype "unspecified"))
      (node (ref "F1") (pin "1") (pinfunction "1_1") (pintype "unspecified"))
      (node (ref "U7") (pin "6") (pinfunction "VIN_6") (pintype "unspecified"))
    )
    (net (code "35") (name "/VBUS_RAW") (class "Default")
      (node (ref "F1") (pin "2") (pinfunction "2_2") (pintype "unspecified"))
      (node (ref "USB2") (pin "A4B9") (pinfunction "VBUS_A4B9") (pintype "unspecified"))
      (node (ref "USB2") (pin "B4A9") (pinfunction "VBUS_B4A9") (pintype "unspecified"))
    )
    (net (code "36") (name "GND") (class "Default")
      (node (ref "C1") (pin "1") (pinfunction "~_1") (pintype "unspecified"))
      (node (ref "C19") (pin "2") (pinfunction "~_2") (pintype "unspecified"))
      (node (ref "C2") (pin "2") (pinfunction "~_2") (pintype "unspecified"))
      (node (ref "C23") (pin "2") (pinfunction "~_2") (pintype "unspecified"))
      (node (ref "C24") (pin "2") (pinfunction "~_2") (pintype "unspecified"))
      (node (ref "C25") (pin "1") (pinfunction "~_1") (pintype "unspecified"))
      (node (ref "C26") (pin "1") (pinfunction "~_1") (pintype "unspecified"))
      (node (ref "C27") (pin "1") (pinfunction "~_1") (pintype "unspecified"))
      (node (ref "C28") (pin "1") (pinfunction "~_1") (pintype "unspecified"))
      (node (ref "C3") (pin "2") (pinfunction "~_2") (pintype "unspecified"))
      (node (ref "C40") (pin "2") (pinfunction "~_2") (pintype "unspecified"))
      (node (ref "C41") (pin "2") (pinfunction "~_2") (pintype "unspecified"))
      (node (ref "C42") (pin "2") (pinfunction "~_2") (pintype "unspecified"))
      (node (ref "C43") (pin "2") (pinfunction "~_2") (pintype "unspecified"))
      (node (ref "C46") (pin "2") (pinfunction "~_2") (pintype "unspecified"))
      (node (ref "C49") (pin "1") (pinfunction "~_1") (pintype "unspecified"))
      (node (ref "C5") (pin "2") (pinfunction "~_2") (pintype "unspecified"))
      (node (ref "C50") (pin "2") (pinfunction "~_2") (pintype "unspecified"))
      (node (ref "C51") (pin "2") (pinfunction "~_2") (pintype "unspecified"))
      (node (ref "C52") (pin "2") (pinfunction "~_2") (pintype "unspecified"))
      (node (ref "C53") (pin "2") (pinfunction "~_2") (pintype "unspecified"))
      (node (ref "C54") (pin "2") (pinfunction "~_2") (pintype "unspecified"))
      (node (ref "C55") (pin "2") (pinfunction "~_2") (pintype "unspecified"))
      (node (ref "C56") (pin "1") (pinfunction "~_1") (pintype "unspecified"))
      (node (ref "C57") (pin "1") (pinfunction "~_1") (pintype "unspecified"))
      (node (ref "C58") (pin "1") (pinfunction "~_1") (pintype "unspecified"))
      (node (ref "C59") (pin "2") (pinfunction "~_2") (pintype "unspecified"))
      (node (ref "C61") (pin "2") (pinfunction "~_2") (pintype "unspecified"))
      (node (ref "C62") (pin "2") (pinfunction "~_2") (pintype "unspecified"))
      (node (ref "C8") (pin "2") (pinfunction "2_2") (pintype "input"))
      (node (ref "CN1") (pin "05") (pinfunction "5_05") (pintype "unspecified"))
      (node (ref "CN1") (pin "07") (pinfunction "7_07") (pintype "unspecified"))
      (node (ref "CN1") (pin "11") (pinfunction "11_11") (pintype "unspecified"))
      (node (ref "D2") (pin "2") (pinfunction "A_2") (pintype "unspecified"))
      (node (ref "FL1") (pin "2") (pinfunction "GND4_2") (pintype "unspecified"))
      (node (ref "FL1") (pin "4") (pinfunction "GND1_4") (pintype "unspecified"))
      (node (ref "FL1") (pin "5") (pinfunction "GND2_5") (pintype "unspecified"))
      (node (ref "FL1") (pin "6") (pinfunction "GND3_6") (pintype "unspecified"))
      (node (ref "KEY1") (pin "1") (pinfunction "1_1") (pintype "unspecified"))
      (node (ref "KEY1") (pin "2") (pinfunction "2_2") (pintype "unspecified"))
      (node (ref "KEY2") (pin "1") (pinfunction "1_1") (pintype "unspecified"))
      (node (ref "KEY2") (pin "2") (pinfunction "2_2") (pintype "unspecified"))
      (node (ref "R1") (pin "1") (pinfunction "~_1") (pintype "unspecified"))
      (node (ref "R10") (pin "2") (pinfunction "2_2") (pintype "input"))
      (node (ref "R20") (pin "2") (pinfunction "~_2") (pintype "unspecified"))
      (node (ref "R42") (pin "1") (pinfunction "~_1") (pintype "unspecified"))
      (node (ref "R8") (pin "1") (pinfunction "1_1") (pintype "input"))
      (node (ref "R9") (pin "1") (pinfunction "1_1") (pintype "input"))
      (node (ref "SW2") (pin "3") (pinfunction "3_3") (pintype "unspecified"))
      (node (ref "U10") (pin "2") (pinfunction "SDX_2") (pintype "unspecified"))
      (node (ref "U10") (pin "3") (pinfunction "SCX_3") (pintype "unspecified"))
      (node (ref "U10") (pin "6") (pinfunction "GND_6") (pintype "unspecified"))
      (node (ref "U10") (pin "7") (pinfunction "GND_7") (pintype "unspecified"))
      (node (ref "U13") (pin "2") (pinfunction "GND_2") (pintype "unspecified"))
      (node (ref "U13") (pin "4") (pinfunction "ADD0_4") (pintype "unspecified"))
      (node (ref "U14") (pin "22") (pinfunction "VSSRF_22") (pintype "unspecified"))
      (node (ref "U14") (pin "32") (pinfunction "VSSSMPS_32") (pintype "unspecified"))
      (node (ref "U14") (pin "49") (pinfunction "EP_49") (pintype "unspecified"))
      (node (ref "U3") (pin "2") (pinfunction "GND_2") (pintype "unspecified"))
      (node (ref "U5") (pin "2") (pinfunction "GND_2") (pintype "unspecified"))
      (node (ref "U5") (pin "3") (pinfunction "CTL_3") (pintype "unspecified"))
      (node (ref "U6") (pin "1") (pinfunction "CTG_1") (pintype "unspecified"))
      (node (ref "U6") (pin "4") (pinfunction "GND_4") (pintype "unspecified"))
      (node (ref "U6") (pin "9") (pinfunction "EP_9") (pintype "unspecified"))
      (node (ref "U7") (pin "5") (pinfunction "GND_5") (pintype "unspecified"))
      (node (ref "U8") (pin "2") (pinfunction "GND_2") (pintype "unspecified"))
      (node (ref "U9") (pin "3") (pinfunction "3_3") (pintype "unspecified"))
      (node (ref "U9") (pin "4") (pinfunction "4_4") (pintype "unspecified"))
      (node (ref "U9") (pin "5") (pinfunction "5_5") (pintype "unspecified"))
      (node (ref "USB2") (pin "A1B12") (pinfunction "GND_A1B12") (pintype "unspecified"))
      (node (ref "USB2") (pin "B1A12") (pinfunction "GND_B1A12") (pintype "unspecified"))
      (node (ref "X1") (pin "2") (pinfunction "GND_2") (pintype "input"))
      (node (ref "X1") (pin "4") (pinfunction "GND_4") (pintype "input"))
    )
    (net (code "37") (name "Net-(D1-C)") (class "Default")
      (node (ref "C2") (pin "1") (pinfunction "~_1") (pintype "unspecified"))
      (node (ref "D1") (pin "1") (pinfunction "C_1") (pintype "unspecified"))
      (node (ref "Q1") (pin "2") (pinfunction "S_2") (pintype "unspecified"))
      (node (ref "U5") (pin "6") (pinfunction "SENSE_6") (pintype "unspecified"))
      (node (ref "U8") (pin "1") (pinfunction "IN_1") (pintype "unspecified"))
      (node (ref "U8") (pin "3") (pinfunction "EN_3") (pintype "unspecified"))
    )
    (net (code "38") (name "Net-(FL1-OUT)") (class "Default")
      (node (ref "C61") (pin "1") (pinfunction "~_1") (pintype "unspecified"))
      (node (ref "FL1") (pin "1") (pinfunction "OUT_1") (pintype "unspecified"))
      (node (ref "R36") (pin "1") (pinfunction "~_1") (pintype "unspecified"))
    )
    (net (code "39") (name "Net-(LED5-Pad1)") (class "Default")
      (node (ref "LED5") (pin "1") (pinfunction "1_1") (pintype "unspecified"))
      (node (ref "R45") (pin "2") (pinfunction "~_2") (pintype "unspecified"))
    )
    (net (code "40") (name "Net-(LED5-Pad4)") (class "Default")
      (node (ref "LED5") (pin "4") (pinfunction "4_4") (pintype "unspecified"))
      (node (ref "R46") (pin "2") (pinfunction "~_2") (pintype "unspecified"))
    )
    (net (code "41") (name "Net-(Q1-G)") (class "Default")
      (node (ref "Q1") (pin "1") (pinfunction "G_1") (pintype "unspecified"))
      (node (ref "U5") (pin "5") (pinfunction "GATE_5") (pintype "unspecified"))
    )
    (net (code "42") (name "Net-(U3-ON)") (class "Default")
      (node (ref "SW2") (pin "2") (pinfunction "2_2") (pintype "unspecified"))
      (node (ref "U3") (pin "3") (pinfunction "ON_3") (pintype "unspecified"))
    )
    (net (code "43") (name "Net-(U3-VIN)") (class "Default")
      (node (ref "C3") (pin "1") (pinfunction "~_1") (pintype "unspecified"))
      (node (ref "SW2") (pin "1") (pinfunction "1_1") (pintype "unspecified"))
      (node (ref "U3") (pin "1") (pinfunction "VIN_1") (pintype "unspecified"))
      (node (ref "U8") (pin "5") (pinfunction "OUT_5") (pintype "unspecified"))
    )
    (net (code "44") (name "Net-(U6-QSTRT)") (class "Default")
      (node (ref "R1") (pin "2") (pinfunction "~_2") (pintype "unspecified"))
      (node (ref "U6") (pin "6") (pinfunction "QSTRT_6") (pintype "unspecified"))
    )
    (net (code "45") (name "Net-(U7-ISET)") (class "Default")
      (node (ref "R20") (pin "1") (pinfunction "~_1") (pintype "unspecified"))
      (node (ref "U7") (pin "4") (pinfunction "ISET_4") (pintype "unspecified"))
    )
    (net (code "46") (name "Net-(U14-PA5)") (class "Default")
      (node (ref "R37") (pin "2") (pinfunction "2_2") (pintype "input"))
      (node (ref "U14") (pin "14") (pinfunction "PA5_14") (pintype "unspecified"))
    )
    (net (code "47") (name "Net-(U14-PA6)") (class "Default")
      (node (ref "R38") (pin "2") (pinfunction "2_2") (pintype "input"))
      (node (ref "U14") (pin "15") (pinfunction "PA6_15") (pintype "unspecified"))
    )
    (net (code "48") (name "Net-(U14-PA7)") (class "Default")
      (node (ref "R39") (pin "2") (pinfunction "2_2") (pintype "input"))
      (node (ref "U14") (pin "16") (pinfunction "PA7_16") (pintype "unspecified"))
    )
    (net (code "49") (name "Net-(U14-PA11)") (class "Default")
      (node (ref "R44") (pin "1") (pinfunction "1_1") (pintype "input"))
      (node (ref "U14") (pin "37") (pinfunction "PA11_37") (pintype "unspecified"))
    )
    (net (code "50") (name "Net-(U14-PA12)") (class "Default")
      (node (ref "R43") (pin "1") (pinfunction "1_1") (pintype "input"))
      (node (ref "U14") (pin "38") (pinfunction "PA12_38") (pintype "unspecified"))
    )
    (net (code "51") (name "Net-(U14-VFBSMPS)") (class "Default")
      (node (ref "C46") (pin "1") (pinfunction "~_1") (pintype "unspecified"))
      (node (ref "L1") (pin "2") (pinfunction "2_2") (pintype "unspecified"))
      (node (ref "U14") (pin "31") (pinfunction "VFBSMPS_31") (pintype "unspecified"))
    )
    (net (code "52") (name "Net-(U14-VLXSMPS)") (class "Default")
      (node (ref "L1") (pin "1") (pinfunction "1_1") (pintype "unspecified"))
      (node (ref "U14") (pin "33") (pinfunction "VLXSMPS_33") (pintype "unspecified"))
    )
    (net (code "53") (name "Net-(U16-ANT)") (class "Default")
      (node (ref "C62") (pin "1") (pinfunction "~_1") (pintype "unspecified"))
      (node (ref "R36") (pin "2") (pinfunction "~_2") (pintype "unspecified"))
      (node (ref "U16") (pin "1") (pinfunction "ANT_1") (pintype "unspecified"))
    )
    (net (code "54") (name "Net-(USB2-CC1)") (class "Default")
      (node (ref "R8") (pin "2") (pinfunction "2_2") (pintype "input"))
      (node (ref "USB2") (pin "A5") (pinfunction "CC1_A5") (pintype "unspecified"))
    )
    (net (code "55") (name "Net-(USB2-CC2)") (class "Default")
      (node (ref "R9") (pin "2") (pinfunction "2_2") (pintype "input"))
      (node (ref "USB2") (pin "B5") (pinfunction "CC2_B5") (pintype "unspecified"))
    )
    (net (code "56") (name "unconnected-(CN1-1-Pad01)") (class "Default")
      (node (ref "CN1") (pin "01") (pinfunction "1_01") (pintype "unspecified+no_connect"))
    )
    (net (code "57") (name "unconnected-(CN1-2-Pad02)") (class "Default")
      (node (ref "CN1") (pin "02") (pinfunction "2_02") (pintype "unspecified+no_connect"))
    )
    (net (code "58") (name "unconnected-(CN1-9-Pad09)") (class "Default")
      (node (ref "CN1") (pin "09") (pinfunction "9_09") (pintype "unspecified+no_connect"))
    )
    (net (code "59") (name "unconnected-(CN1-Pad10)") (class "Default")
      (node (ref "CN1") (pin "10") (pinfunction "10_10") (pintype "unspecified+no_connect"))
    )
    (net (code "60") (name "unconnected-(LED5-Pad3)") (class "Default")
      (node (ref "LED5") (pin "3") (pinfunction "3_3") (pintype "unspecified+no_connect"))
    )
    (net (code "61") (name "unconnected-(U3-CT-Pad4)") (class "Default")
      (node (ref "U3") (pin "4") (pinfunction "CT_4") (pintype "unspecified+no_connect"))
    )
    (net (code "62") (name "unconnected-(U3-QOD-Pad5)") (class "Default")
      (node (ref "U3") (pin "5") (pinfunction "QOD_5") (pintype "unspecified+no_connect"))
    )
    (net (code "63") (name "unconnected-(U8-NC-Pad4)") (class "Default")
      (node (ref "U8") (pin "4") (pinfunction "NC_4") (pintype "unspecified+no_connect"))
    )
    (net (code "64") (name "unconnected-(U10-OSC_AUX-Pad10)") (class "Default")
      (node (ref "U10") (pin "10") (pinfunction "OSC_AUX_10") (pintype "unspecified+no_connect"))
    )
    (net (code "65") (name "unconnected-(U10-SDO_AUX-Pad11)") (class "Default")
      (node (ref "U10") (pin "11") (pinfunction "SDO_AUX_11") (pintype "unspecified+no_connect"))
    )
    (net (code "66") (name "unconnected-(U13-EP-Pad7)") (class "Default")
      (node (ref "U13") (pin "7") (pinfunction "EP_7") (pintype "unspecified+no_connect"))
    )
    (net (code "67") (name "unconnected-(U14-AT0-Pad26)") (class "Default")
      (node (ref "U14") (pin "26") (pinfunction "AT0_26") (pintype "unspecified+no_connect"))
    )
    (net (code "68") (name "unconnected-(U14-AT1-Pad27)") (class "Default")
      (node (ref "U14") (pin "27") (pinfunction "AT1_27") (pintype "unspecified+no_connect"))
    )
    (net (code "69") (name "unconnected-(U14-PA15-Pad42)") (class "Default")
      (node (ref "U14") (pin "42") (pinfunction "PA15_42") (pintype "unspecified+no_connect"))
    )
    (net (code "70") (name "unconnected-(U14-PB0-Pad28)") (class "Default")
      (node (ref "U14") (pin "28") (pinfunction "PB0_28") (pintype "unspecified+no_connect"))
    )
    (net (code "71") (name "unconnected-(U14-PB1-Pad29)") (class "Default")
      (node (ref "U14") (pin "29") (pinfunction "PB1_29") (pintype "unspecified+no_connect"))
    )
    (net (code "72") (name "unconnected-(U14-PB4-Pad44)") (class "Default")
      (node (ref "U14") (pin "44") (pinfunction "PB4_44") (pintype "unspecified+no_connect"))
    )
    (net (code "73") (name "unconnected-(U14-PB5-Pad45)") (class "Default")
      (node (ref "U14") (pin "45") (pinfunction "PB5_45") (pintype "unspecified+no_connect"))
    )
    (net (code "74") (name "unconnected-(U16-Pad2)") (class "Default")
      (node (ref "U16") (pin "2") (pinfunction "2_2") (pintype "unspecified+no_connect"))
    )
    (net (code "75") (name "unconnected-(USB2-SBU1-PadA8)") (class "Default")
      (node (ref "USB2") (pin "A8") (pinfunction "SBU1_A8") (pintype "unspecified+no_connect"))
    )
    (net (code "76") (name "unconnected-(USB2-SBU2-PadB8)") (class "Default")
      (node (ref "USB2") (pin "B8") (pinfunction "SBU2_B8") (pintype "unspecified+no_connect"))
    )
  )
)
